# sensor_interface_1_1_0.net
KiCad netlist of a schematic drawn in EAGLE
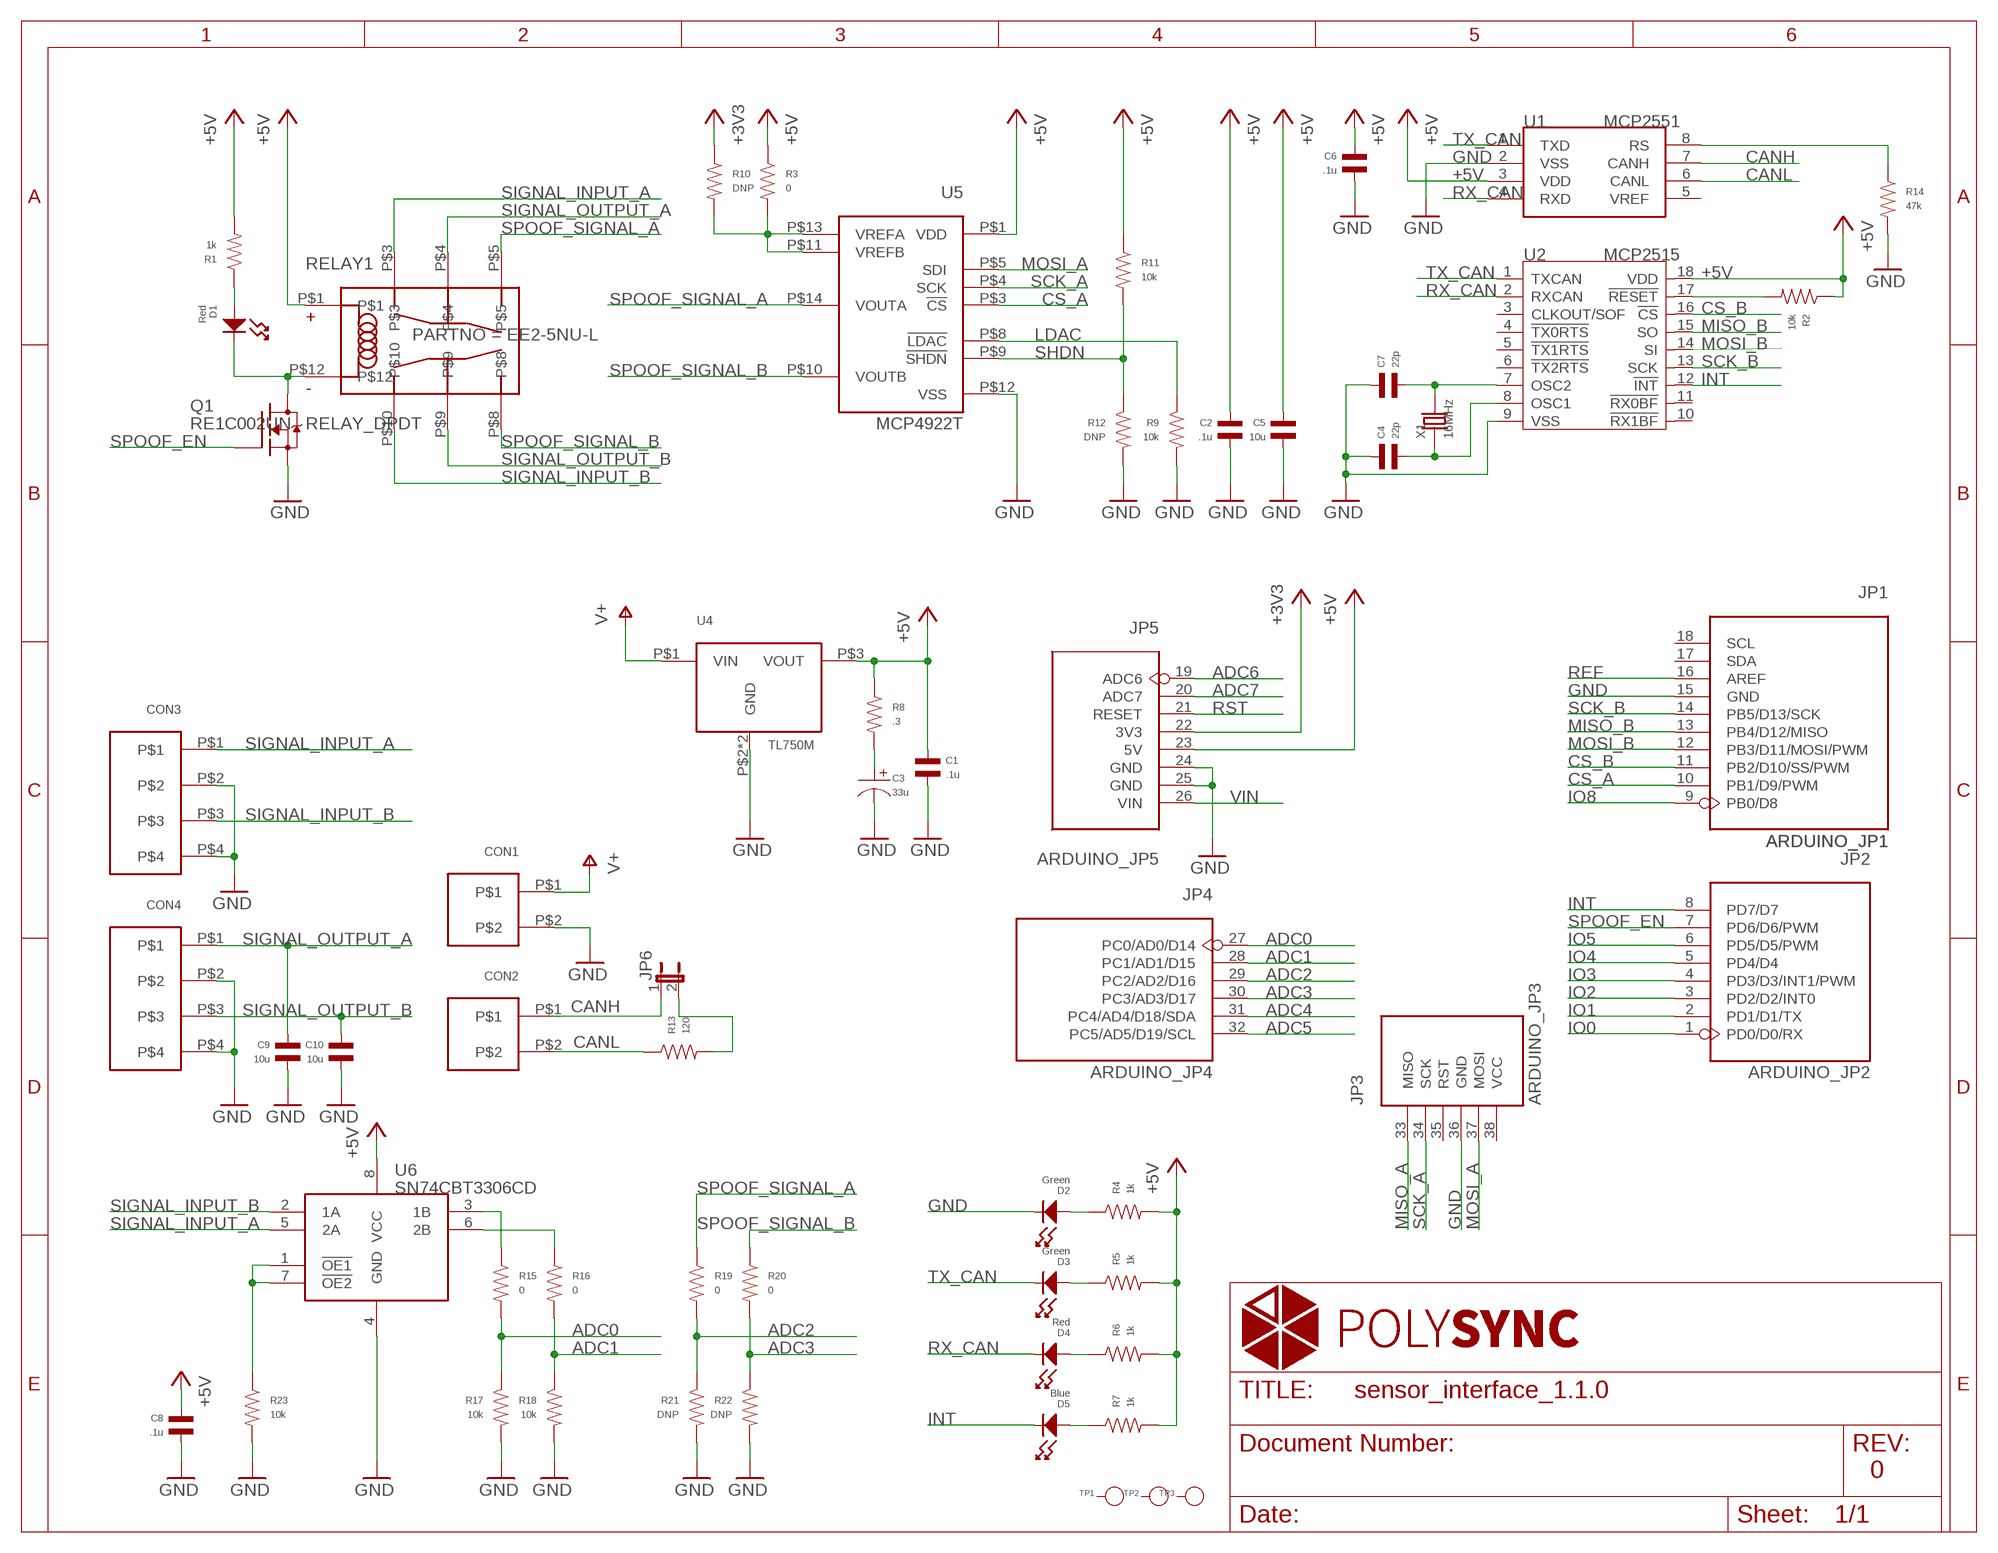
[diagram p0: schematic, sheet 1]

(export (version "E")
  (design (tool "Eeschema 10.0.6"))
  (components
    (comp (ref "C1")
      (value ".1u")
      (footprint "eagle-import:C0402")
      (libsource (lib "eagle-import") (part "CAPACITOR_NP_0402"))
    )
    (comp (ref "C2")
      (value ".1u")
      (footprint "eagle-import:C0402")
      (libsource (lib "eagle-import") (part "CAPACITOR_NP_0402"))
    )
    (comp (ref "C3")
      (value "33u")
      (footprint "eagle-import:CP1206")
      (libsource (lib "eagle-import") (part "CAPACITOR_P"))
    )
    (comp (ref "C4")
      (value "22p")
      (footprint "eagle-import:C0402")
      (libsource (lib "eagle-import") (part "CAPACITOR_NP_0402"))
    )
    (comp (ref "C5")
      (value "10u")
      (footprint "eagle-import:C0805")
      (libsource (lib "eagle-import") (part "CAPACITOR_NP_0805"))
    )
    (comp (ref "C6")
      (value ".1u")
      (footprint "eagle-import:C0402")
      (libsource (lib "eagle-import") (part "CAPACITOR_NP_0402"))
    )
    (comp (ref "C7")
      (value "22p")
      (footprint "eagle-import:C0402")
      (libsource (lib "eagle-import") (part "CAPACITOR_NP_0402"))
    )
    (comp (ref "C8")
      (value ".1u")
      (footprint "eagle-import:C0402")
      (libsource (lib "eagle-import") (part "CAPACITOR_NP_0402"))
    )
    (comp (ref "C9")
      (value "10u")
      (footprint "eagle-import:C0805")
      (libsource (lib "eagle-import") (part "CAPACITOR_NP_0805"))
    )
    (comp (ref "C10")
      (value "10u")
      (footprint "eagle-import:C0805")
      (libsource (lib "eagle-import") (part "CAPACITOR_NP_0805"))
    )
    (comp (ref "CON1")
      (value "CON23.5MM")
      (footprint "eagle-import:PHOENIX_2_45")
      (libsource (lib "eagle-import") (part "CON23.5MM"))
    )
    (comp (ref "CON2")
      (value "CON23.5MM")
      (footprint "eagle-import:PHOENIX_2_45")
      (libsource (lib "eagle-import") (part "CON23.5MM"))
    )
    (comp (ref "CON3")
      (value "CON4")
      (footprint "eagle-import:PHOENIX_4_45")
      (libsource (lib "eagle-import") (part "CON4"))
    )
    (comp (ref "CON4")
      (value "CON4")
      (footprint "eagle-import:PHOENIX_4_45")
      (libsource (lib "eagle-import") (part "CON4"))
    )
    (comp (ref "D1")
      (value "Red")
      (footprint "eagle-import:LED0603")
      (fields (field (name "HOUSEPART") "NO"))
      (libsource (lib "eagle-import") (part "LED_SINGLE-0603"))
    )
    (comp (ref "D2")
      (value "Green")
      (footprint "eagle-import:LED0603")
      (fields (field (name "HOUSEPART") "NO"))
      (libsource (lib "eagle-import") (part "LED_SINGLE-0603"))
    )
    (comp (ref "D3")
      (value "Green")
      (footprint "eagle-import:LED0603")
      (fields (field (name "HOUSEPART") "NO"))
      (libsource (lib "eagle-import") (part "LED_SINGLE-0603"))
    )
    (comp (ref "D4")
      (value "Red")
      (footprint "eagle-import:LED0603")
      (fields (field (name "HOUSEPART") "NO"))
      (libsource (lib "eagle-import") (part "LED_SINGLE-0603"))
    )
    (comp (ref "D5")
      (value "Blue")
      (footprint "eagle-import:LED0603")
      (fields (field (name "HOUSEPART") "NO"))
      (libsource (lib "eagle-import") (part "LED_SINGLE-0603"))
    )
    (comp (ref "JP1")
      (value "ARDUINO_JP1")
      (footprint "eagle-import:ARDUINO_JP1")
      (libsource (lib "eagle-import") (part "ARDUINO_JP1"))
    )
    (comp (ref "JP2")
      (value "ARDUINO_JP2")
      (footprint "eagle-import:ARDUINO_JP2")
      (libsource (lib "eagle-import") (part "ARDUINO_JP2"))
    )
    (comp (ref "JP3")
      (value "ARDUINO_JP3")
      (footprint "eagle-import:ARDUINO_JP3")
      (libsource (lib "eagle-import") (part "ARDUINO_JP3"))
    )
    (comp (ref "JP4")
      (value "ARDUINO_JP4")
      (footprint "eagle-import:ARDUINO_JP4")
      (libsource (lib "eagle-import") (part "ARDUINO_JP4"))
    )
    (comp (ref "JP5")
      (value "ARDUINO_JP5")
      (footprint "eagle-import:ARDUINO_JP5")
      (libsource (lib "eagle-import") (part "ARDUINO_JP5"))
    )
    (comp (ref "JP6")
      (value "JP1E")
      (footprint "eagle-import:JP1")
      (libsource (lib "eagle-import") (part "JP1E"))
    )
    (comp (ref "Q1")
      (value "RE1C002UN")
      (footprint "eagle-import:EMT3F")
      (libsource (lib "eagle-import") (part "RE1C002UN"))
    )
    (comp (ref "R1")
      (value "1k")
      (footprint "eagle-import:R0402")
      (libsource (lib "eagle-import") (part "RESISTOR_0402"))
    )
    (comp (ref "R2")
      (value "10k")
      (footprint "eagle-import:R0402")
      (libsource (lib "eagle-import") (part "RESISTOR_0402"))
    )
    (comp (ref "R3")
      (value "0")
      (footprint "eagle-import:R0402")
      (libsource (lib "eagle-import") (part "RESISTOR_0402"))
    )
    (comp (ref "R4")
      (value "1k")
      (footprint "eagle-import:R0402")
      (libsource (lib "eagle-import") (part "RESISTOR_0402"))
    )
    (comp (ref "R5")
      (value "1k")
      (footprint "eagle-import:R0402")
      (libsource (lib "eagle-import") (part "RESISTOR_0402"))
    )
    (comp (ref "R6")
      (value "1k")
      (footprint "eagle-import:R0402")
      (libsource (lib "eagle-import") (part "RESISTOR_0402"))
    )
    (comp (ref "R7")
      (value "1k")
      (footprint "eagle-import:R0402")
      (libsource (lib "eagle-import") (part "RESISTOR_0402"))
    )
    (comp (ref "R8")
      (value ".3")
      (footprint "eagle-import:R0402")
      (libsource (lib "eagle-import") (part "RESISTOR_0402"))
    )
    (comp (ref "R9")
      (value "10k")
      (footprint "eagle-import:R0402")
      (libsource (lib "eagle-import") (part "RESISTOR_0402"))
    )
    (comp (ref "R10")
      (value "DNP")
      (footprint "eagle-import:R0402")
      (libsource (lib "eagle-import") (part "RESISTOR_0402"))
    )
    (comp (ref "R11")
      (value "10k")
      (footprint "eagle-import:R0402")
      (libsource (lib "eagle-import") (part "RESISTOR_0402"))
    )
    (comp (ref "R12")
      (value "DNP")
      (footprint "eagle-import:R0402")
      (libsource (lib "eagle-import") (part "RESISTOR_0402"))
    )
    (comp (ref "R13")
      (value "120")
      (footprint "eagle-import:R0402")
      (libsource (lib "eagle-import") (part "RESISTOR_0402"))
    )
    (comp (ref "R14")
      (value "47k")
      (footprint "eagle-import:R0402")
      (libsource (lib "eagle-import") (part "RESISTOR_0402"))
    )
    (comp (ref "R15")
      (value "0")
      (footprint "eagle-import:R0402")
      (libsource (lib "eagle-import") (part "RESISTOR_0402"))
    )
    (comp (ref "R16")
      (value "0")
      (footprint "eagle-import:R0402")
      (libsource (lib "eagle-import") (part "RESISTOR_0402"))
    )
    (comp (ref "R17")
      (value "10k")
      (footprint "eagle-import:R0402")
      (libsource (lib "eagle-import") (part "RESISTOR_0402"))
    )
    (comp (ref "R18")
      (value "10k")
      (footprint "eagle-import:R0402")
      (libsource (lib "eagle-import") (part "RESISTOR_0402"))
    )
    (comp (ref "R19")
      (value "0")
      (footprint "eagle-import:R0402")
      (libsource (lib "eagle-import") (part "RESISTOR_0402"))
    )
    (comp (ref "R20")
      (value "0")
      (footprint "eagle-import:R0402")
      (libsource (lib "eagle-import") (part "RESISTOR_0402"))
    )
    (comp (ref "R21")
      (value "DNP")
      (footprint "eagle-import:R0402")
      (libsource (lib "eagle-import") (part "RESISTOR_0402"))
    )
    (comp (ref "R22")
      (value "DNP")
      (footprint "eagle-import:R0402")
      (libsource (lib "eagle-import") (part "RESISTOR_0402"))
    )
    (comp (ref "R23")
      (value "10k")
      (footprint "eagle-import:R0402")
      (libsource (lib "eagle-import") (part "RESISTOR_0402"))
    )
    (comp (ref "RELAY1")
      (value "RELAY_DPDT")
      (footprint "eagle-import:KEMET_EE2")
      (fields (field (name "PARTNO") "EE2-5NU-L"))
      (libsource (lib "eagle-import") (part "RELAY_DPDT"))
    )
    (comp (ref "TP1")
      (value "PAD-TEST-POINT'4545'")
      (footprint "eagle-import:TP_4545")
      (fields (field (name "PARTNO") "DNP"))
      (libsource (lib "eagle-import") (part "PAD-TEST-POINT'4545'"))
    )
    (comp (ref "TP2")
      (value "PAD-TEST-POINT'4545'")
      (footprint "eagle-import:TP_4545")
      (fields (field (name "PARTNO") "DNP"))
      (libsource (lib "eagle-import") (part "PAD-TEST-POINT'4545'"))
    )
    (comp (ref "TP3")
      (value "PAD-TEST-POINT'4545'")
      (footprint "eagle-import:TP_4545")
      (fields (field (name "PARTNO") "DNP"))
      (libsource (lib "eagle-import") (part "PAD-TEST-POINT'4545'"))
    )
    (comp (ref "U1")
      (value "MCP2551")
      (footprint "eagle-import:SOIC8-6.0")
      (libsource (lib "eagle-import") (part "MCP2551-SOIC8"))
    )
    (comp (ref "U2")
      (value "MCP2515")
      (footprint "eagle-import:SOIC18")
      (libsource (lib "eagle-import") (part "MCP2515-SOIC18"))
    )
    (comp (ref "U4")
      (value "TL750M")
      (footprint "eagle-import:TO-263")
      (libsource (lib "eagle-import") (part "TL750M"))
    )
    (comp (ref "U5")
      (value "MCP4922T")
      (footprint "eagle-import:TSSOP-14")
      (libsource (lib "eagle-import") (part "MCP4922T"))
    )
    (comp (ref "U6")
      (value "SN74CBT3306CD")
      (footprint "eagle-import:SOIC-8")
      (libsource (lib "eagle-import") (part "SN74CBT3306CD"))
    )
    (comp (ref "X1")
      (value "16MHz")
      (footprint "eagle-import:HC49UP")
      (libsource (lib "eagle-import") (part "CRYSTAL-HC49UP"))
    )
  )
  (nets
    (net (code "1") (name "+3V3") (class "Default")
      (node (ref "JP5") (pin "22") (pinfunction "3V3_22") (pintype "bidirectional"))
      (node (ref "R10") (pin "P$1") (pinfunction "P$1_P$1") (pintype "passive"))
    )
    (net (code "2") (name "+5V") (class "Default")
      (node (ref "C1") (pin "P$1") (pinfunction "P$1_P$1") (pintype "passive"))
      (node (ref "C2") (pin "P$1") (pinfunction "P$1_P$1") (pintype "passive"))
      (node (ref "C5") (pin "P$1") (pinfunction "P$1_P$1") (pintype "passive"))
      (node (ref "C6") (pin "P$1") (pinfunction "P$1_P$1") (pintype "passive"))
      (node (ref "C8") (pin "P$1") (pinfunction "P$1_P$1") (pintype "passive"))
      (node (ref "JP5") (pin "23") (pinfunction "5V_23") (pintype "bidirectional"))
      (node (ref "R1") (pin "P$2") (pinfunction "P$2_P$2") (pintype "passive"))
      (node (ref "R11") (pin "P$1") (pinfunction "P$1_P$1") (pintype "passive"))
      (node (ref "R2") (pin "P$1") (pinfunction "P$1_P$1") (pintype "passive"))
      (node (ref "R3") (pin "P$1") (pinfunction "P$1_P$1") (pintype "passive"))
      (node (ref "R4") (pin "P$2") (pinfunction "P$2_P$2") (pintype "passive"))
      (node (ref "R5") (pin "P$2") (pinfunction "P$2_P$2") (pintype "passive"))
      (node (ref "R6") (pin "P$2") (pinfunction "P$2_P$2") (pintype "passive"))
      (node (ref "R7") (pin "P$2") (pinfunction "P$2_P$2") (pintype "passive"))
      (node (ref "R8") (pin "P$1") (pinfunction "P$1_P$1") (pintype "passive"))
      (node (ref "RELAY1") (pin "P$1") (pinfunction "P$1_P$1") (pintype "bidirectional"))
      (node (ref "U1") (pin "3") (pinfunction "VDD_3") (pintype "bidirectional"))
      (node (ref "U2") (pin "18") (pinfunction "VDD_18") (pintype "power_in"))
      (node (ref "U4") (pin "P$3") (pinfunction "VOUT_P$3") (pintype "bidirectional"))
      (node (ref "U5") (pin "P$1") (pinfunction "VDD_P$1") (pintype "bidirectional"))
      (node (ref "U6") (pin "8") (pinfunction "VCC_8") (pintype "bidirectional"))
    )
    (net (code "3") (name "/ADC0") (class "Default")
      (node (ref "JP4") (pin "27") (pinfunction "PC0/AD0/D14_27") (pintype "bidirectional"))
      (node (ref "R15") (pin "P$2") (pinfunction "P$2_P$2") (pintype "passive"))
      (node (ref "R17") (pin "P$1") (pinfunction "P$1_P$1") (pintype "passive"))
    )
    (net (code "4") (name "/ADC1") (class "Default")
      (node (ref "JP4") (pin "28") (pinfunction "PC1/AD1/D15_28") (pintype "bidirectional"))
      (node (ref "R16") (pin "P$2") (pinfunction "P$2_P$2") (pintype "passive"))
      (node (ref "R18") (pin "P$1") (pinfunction "P$1_P$1") (pintype "passive"))
    )
    (net (code "5") (name "/ADC2") (class "Default")
      (node (ref "JP4") (pin "29") (pinfunction "PC2/AD2/D16_29") (pintype "bidirectional"))
      (node (ref "R19") (pin "P$2") (pinfunction "P$2_P$2") (pintype "passive"))
      (node (ref "R21") (pin "P$1") (pinfunction "P$1_P$1") (pintype "passive"))
    )
    (net (code "6") (name "/ADC3") (class "Default")
      (node (ref "JP4") (pin "30") (pinfunction "PC3/AD3/D17_30") (pintype "bidirectional"))
      (node (ref "R20") (pin "P$2") (pinfunction "P$2_P$2") (pintype "passive"))
      (node (ref "R22") (pin "P$1") (pinfunction "P$1_P$1") (pintype "passive"))
    )
    (net (code "7") (name "/ADC4") (class "Default")
      (node (ref "JP4") (pin "31") (pinfunction "PC4/AD4/D18/SDA_31") (pintype "bidirectional"))
    )
    (net (code "8") (name "/ADC5") (class "Default")
      (node (ref "JP4") (pin "32") (pinfunction "PC5/AD5/D19/SCL_32") (pintype "bidirectional"))
    )
    (net (code "9") (name "/ADC6") (class "Default")
      (node (ref "JP5") (pin "19") (pinfunction "ADC6_19") (pintype "bidirectional"))
    )
    (net (code "10") (name "/ADC7") (class "Default")
      (node (ref "JP5") (pin "20") (pinfunction "ADC7_20") (pintype "bidirectional"))
    )
    (net (code "11") (name "/CANH") (class "Default")
      (node (ref "CON2") (pin "P$1") (pinfunction "P$1_P$1") (pintype "bidirectional"))
      (node (ref "JP6") (pin "1") (pinfunction "1_1") (pintype "passive"))
      (node (ref "U1") (pin "7") (pinfunction "CANH_7") (pintype "bidirectional"))
    )
    (net (code "12") (name "/CANL") (class "Default")
      (node (ref "CON2") (pin "P$2") (pinfunction "P$2_P$2") (pintype "bidirectional"))
      (node (ref "R13") (pin "P$1") (pinfunction "P$1_P$1") (pintype "passive"))
      (node (ref "U1") (pin "6") (pinfunction "CANL_6") (pintype "bidirectional"))
    )
    (net (code "13") (name "/CS_A") (class "Default")
      (node (ref "JP1") (pin "10") (pinfunction "PB1/D9/PWM_10") (pintype "bidirectional"))
      (node (ref "U5") (pin "P$3") (pinfunction "~{CS}_P$3") (pintype "bidirectional"))
    )
    (net (code "14") (name "/CS_B") (class "Default")
      (node (ref "JP1") (pin "11") (pinfunction "PB2/D10/SS/PWM_11") (pintype "bidirectional"))
      (node (ref "U2") (pin "16") (pinfunction "~{CS}_16") (pintype "input"))
    )
    (net (code "15") (name "/INT") (class "Default")
      (node (ref "D5") (pin "CATHODE") (pinfunction "CATHODE_CATHODE") (pintype "power_in"))
      (node (ref "JP2") (pin "8") (pinfunction "PD7/D7_8") (pintype "bidirectional"))
      (node (ref "U2") (pin "12") (pinfunction "~{INT}_12") (pintype "output"))
    )
    (net (code "16") (name "/IO0") (class "Default")
      (node (ref "JP2") (pin "1") (pinfunction "PD0/D0/RX_1") (pintype "bidirectional"))
    )
    (net (code "17") (name "/IO1") (class "Default")
      (node (ref "JP2") (pin "2") (pinfunction "PD1/D1/TX_2") (pintype "bidirectional"))
    )
    (net (code "18") (name "/IO2") (class "Default")
      (node (ref "JP2") (pin "3") (pinfunction "PD2/D2/INT0_3") (pintype "bidirectional"))
    )
    (net (code "19") (name "/IO3") (class "Default")
      (node (ref "JP2") (pin "4") (pinfunction "PD3/D3/INT1/PWM_4") (pintype "bidirectional"))
    )
    (net (code "20") (name "/IO4") (class "Default")
      (node (ref "JP2") (pin "5") (pinfunction "PD4/D4_5") (pintype "bidirectional"))
    )
    (net (code "21") (name "/IO5") (class "Default")
      (node (ref "JP2") (pin "6") (pinfunction "PD5/D5/PWM_6") (pintype "bidirectional"))
    )
    (net (code "22") (name "/IO8") (class "Default")
      (node (ref "JP1") (pin "9") (pinfunction "PB0/D8_9") (pintype "bidirectional"))
    )
    (net (code "23") (name "/LDAC") (class "Default")
      (node (ref "R9") (pin "P$1") (pinfunction "P$1_P$1") (pintype "passive"))
      (node (ref "U5") (pin "P$8") (pinfunction "~{LDAC}_P$8") (pintype "bidirectional"))
    )
    (net (code "24") (name "/MISO_A") (class "Default")
      (node (ref "JP3") (pin "33") (pinfunction "MISO_33") (pintype "bidirectional"))
    )
    (net (code "25") (name "/MISO_B") (class "Default")
      (node (ref "JP1") (pin "13") (pinfunction "PB4/D12/MISO_13") (pintype "bidirectional"))
      (node (ref "U2") (pin "15") (pinfunction "SO_15") (pintype "output"))
    )
    (net (code "26") (name "/MOSI_A") (class "Default")
      (node (ref "JP3") (pin "37") (pinfunction "MOSI_37") (pintype "bidirectional"))
      (node (ref "U5") (pin "P$5") (pinfunction "SDI_P$5") (pintype "bidirectional"))
    )
    (net (code "27") (name "/MOSI_B") (class "Default")
      (node (ref "JP1") (pin "12") (pinfunction "PB3/D11/MOSI/PWM_12") (pintype "bidirectional"))
      (node (ref "U2") (pin "14") (pinfunction "SI_14") (pintype "input"))
    )
    (net (code "28") (name "/REF") (class "Default")
      (node (ref "JP1") (pin "16") (pinfunction "AREF_16") (pintype "bidirectional"))
    )
    (net (code "29") (name "/RST") (class "Default")
      (node (ref "JP5") (pin "21") (pinfunction "RESET_21") (pintype "bidirectional"))
    )
    (net (code "30") (name "/RX_CAN") (class "Default")
      (node (ref "D4") (pin "CATHODE") (pinfunction "CATHODE_CATHODE") (pintype "power_in"))
      (node (ref "U1") (pin "4") (pinfunction "RXD_4") (pintype "bidirectional"))
      (node (ref "U2") (pin "2") (pinfunction "RXCAN_2") (pintype "input"))
    )
    (net (code "31") (name "/SCK_A") (class "Default")
      (node (ref "JP3") (pin "34") (pinfunction "SCK_34") (pintype "bidirectional"))
      (node (ref "U5") (pin "P$4") (pinfunction "SCK_P$4") (pintype "bidirectional"))
    )
    (net (code "32") (name "/SCK_B") (class "Default")
      (node (ref "JP1") (pin "14") (pinfunction "PB5/D13/SCK_14") (pintype "bidirectional"))
      (node (ref "U2") (pin "13") (pinfunction "SCK_13") (pintype "input"))
    )
    (net (code "33") (name "/SHDN") (class "Default")
      (node (ref "R11") (pin "P$2") (pinfunction "P$2_P$2") (pintype "passive"))
      (node (ref "R12") (pin "P$1") (pinfunction "P$1_P$1") (pintype "passive"))
      (node (ref "U5") (pin "P$9") (pinfunction "~{SHDN}_P$9") (pintype "bidirectional"))
    )
    (net (code "34") (name "/SIGNAL_INPUT_A") (class "Default")
      (node (ref "CON3") (pin "P$1") (pinfunction "P$1_P$1") (pintype "bidirectional"))
      (node (ref "RELAY1") (pin "P$3") (pinfunction "P$3_P$3") (pintype "bidirectional"))
      (node (ref "U6") (pin "5") (pinfunction "2A_5") (pintype "bidirectional"))
    )
    (net (code "35") (name "/SIGNAL_INPUT_B") (class "Default")
      (node (ref "CON3") (pin "P$3") (pinfunction "P$3_P$3") (pintype "bidirectional"))
      (node (ref "RELAY1") (pin "P$10") (pinfunction "P$10_P$10") (pintype "bidirectional"))
      (node (ref "U6") (pin "2") (pinfunction "1A_2") (pintype "bidirectional"))
    )
    (net (code "36") (name "/SIGNAL_OUTPUT_A") (class "Default")
      (node (ref "C9") (pin "P$1") (pinfunction "P$1_P$1") (pintype "passive"))
      (node (ref "CON4") (pin "P$1") (pinfunction "P$1_P$1") (pintype "bidirectional"))
      (node (ref "RELAY1") (pin "P$4") (pinfunction "P$4_P$4") (pintype "bidirectional"))
    )
    (net (code "37") (name "/SIGNAL_OUTPUT_B") (class "Default")
      (node (ref "C10") (pin "P$1") (pinfunction "P$1_P$1") (pintype "passive"))
      (node (ref "CON4") (pin "P$3") (pinfunction "P$3_P$3") (pintype "bidirectional"))
      (node (ref "RELAY1") (pin "P$9") (pinfunction "P$9_P$9") (pintype "bidirectional"))
    )
    (net (code "38") (name "/SPOOF_EN") (class "Default")
      (node (ref "JP2") (pin "7") (pinfunction "PD6/D6/PWM_7") (pintype "bidirectional"))
      (node (ref "Q1") (pin "P$1") (pinfunction "G_P$1") (pintype "passive"))
    )
    (net (code "39") (name "/SPOOF_SIGNAL_A") (class "Default")
      (node (ref "R19") (pin "P$1") (pinfunction "P$1_P$1") (pintype "passive"))
      (node (ref "RELAY1") (pin "P$5") (pinfunction "P$5_P$5") (pintype "bidirectional"))
      (node (ref "U5") (pin "P$14") (pinfunction "VOUTA_P$14") (pintype "bidirectional"))
    )
    (net (code "40") (name "/SPOOF_SIGNAL_B") (class "Default")
      (node (ref "R20") (pin "P$1") (pinfunction "P$1_P$1") (pintype "passive"))
      (node (ref "RELAY1") (pin "P$8") (pinfunction "P$8_P$8") (pintype "bidirectional"))
      (node (ref "U5") (pin "P$10") (pinfunction "VOUTB_P$10") (pintype "bidirectional"))
    )
    (net (code "41") (name "/TX_CAN") (class "Default")
      (node (ref "D3") (pin "CATHODE") (pinfunction "CATHODE_CATHODE") (pintype "power_in"))
      (node (ref "U1") (pin "1") (pinfunction "TXD_1") (pintype "bidirectional"))
      (node (ref "U2") (pin "1") (pinfunction "TXCAN_1") (pintype "output"))
    )
    (net (code "42") (name "/VIN") (class "Default")
      (node (ref "JP5") (pin "26") (pinfunction "VIN_26") (pintype "bidirectional"))
    )
    (net (code "43") (name "GND") (class "Default")
      (node (ref "C1") (pin "P$2") (pinfunction "P$2_P$2") (pintype "passive"))
      (node (ref "C10") (pin "P$2") (pinfunction "P$2_P$2") (pintype "passive"))
      (node (ref "C2") (pin "P$2") (pinfunction "P$2_P$2") (pintype "passive"))
      (node (ref "C3") (pin "P$2") (pinfunction "P$2_P$2") (pintype "passive"))
      (node (ref "C4") (pin "P$1") (pinfunction "P$1_P$1") (pintype "passive"))
      (node (ref "C5") (pin "P$2") (pinfunction "P$2_P$2") (pintype "passive"))
      (node (ref "C6") (pin "P$2") (pinfunction "P$2_P$2") (pintype "passive"))
      (node (ref "C7") (pin "P$1") (pinfunction "P$1_P$1") (pintype "passive"))
      (node (ref "C8") (pin "P$2") (pinfunction "P$2_P$2") (pintype "passive"))
      (node (ref "C9") (pin "P$2") (pinfunction "P$2_P$2") (pintype "passive"))
      (node (ref "CON1") (pin "P$2") (pinfunction "P$2_P$2") (pintype "bidirectional"))
      (node (ref "CON3") (pin "P$2") (pinfunction "P$2_P$2") (pintype "bidirectional"))
      (node (ref "CON3") (pin "P$4") (pinfunction "P$4_P$4") (pintype "bidirectional"))
      (node (ref "CON4") (pin "P$2") (pinfunction "P$2_P$2") (pintype "bidirectional"))
      (node (ref "CON4") (pin "P$4") (pinfunction "P$4_P$4") (pintype "bidirectional"))
      (node (ref "D2") (pin "CATHODE") (pinfunction "CATHODE_CATHODE") (pintype "power_in"))
      (node (ref "JP1") (pin "15") (pinfunction "GND_15") (pintype "bidirectional"))
      (node (ref "JP3") (pin "36") (pinfunction "GND_36") (pintype "bidirectional"))
      (node (ref "JP5") (pin "24") (pinfunction "GND_24") (pintype "bidirectional"))
      (node (ref "JP5") (pin "25") (pinfunction "GND_25") (pintype "bidirectional"))
      (node (ref "Q1") (pin "P$2") (pinfunction "S_P$2") (pintype "passive"))
      (node (ref "R12") (pin "P$2") (pinfunction "P$2_P$2") (pintype "passive"))
      (node (ref "R14") (pin "P$2") (pinfunction "P$2_P$2") (pintype "passive"))
      (node (ref "R17") (pin "P$2") (pinfunction "P$2_P$2") (pintype "passive"))
      (node (ref "R18") (pin "P$2") (pinfunction "P$2_P$2") (pintype "passive"))
      (node (ref "R21") (pin "P$2") (pinfunction "P$2_P$2") (pintype "passive"))
      (node (ref "R22") (pin "P$2") (pinfunction "P$2_P$2") (pintype "passive"))
      (node (ref "R23") (pin "P$2") (pinfunction "P$2_P$2") (pintype "passive"))
      (node (ref "R9") (pin "P$2") (pinfunction "P$2_P$2") (pintype "passive"))
      (node (ref "U1") (pin "2") (pinfunction "VSS_2") (pintype "bidirectional"))
      (node (ref "U2") (pin "9") (pinfunction "VSS_9") (pintype "power_in"))
      (node (ref "U4") (pin "P$2") (pinfunction "GND_P$2") (pintype "bidirectional"))
      (node (ref "U4") (pin "P$4") (pinfunction "GND_P$4") (pintype "bidirectional"))
      (node (ref "U5") (pin "P$12") (pinfunction "VSS_P$12") (pintype "bidirectional"))
      (node (ref "U6") (pin "4") (pinfunction "GND_4") (pintype "bidirectional"))
    )
    (net (code "44") (name "Net-(C3-PadP$1)") (class "Default")
      (node (ref "C3") (pin "P$1") (pinfunction "P$1_P$1") (pintype "passive"))
      (node (ref "R8") (pin "P$2") (pinfunction "P$2_P$2") (pintype "passive"))
    )
    (net (code "45") (name "Net-(D1-PadANODE)") (class "Default")
      (node (ref "D1") (pin "ANODE") (pinfunction "ANODE_ANODE") (pintype "power_in"))
      (node (ref "R1") (pin "P$1") (pinfunction "P$1_P$1") (pintype "passive"))
    )
    (net (code "46") (name "Net-(D2-PadANODE)") (class "Default")
      (node (ref "D2") (pin "ANODE") (pinfunction "ANODE_ANODE") (pintype "power_in"))
      (node (ref "R4") (pin "P$1") (pinfunction "P$1_P$1") (pintype "passive"))
    )
    (net (code "47") (name "Net-(D3-PadANODE)") (class "Default")
      (node (ref "D3") (pin "ANODE") (pinfunction "ANODE_ANODE") (pintype "power_in"))
      (node (ref "R5") (pin "P$1") (pinfunction "P$1_P$1") (pintype "passive"))
    )
    (net (code "48") (name "Net-(D4-PadANODE)") (class "Default")
      (node (ref "D4") (pin "ANODE") (pinfunction "ANODE_ANODE") (pintype "power_in"))
      (node (ref "R6") (pin "P$1") (pinfunction "P$1_P$1") (pintype "passive"))
    )
    (net (code "49") (name "Net-(D5-PadANODE)") (class "Default")
      (node (ref "D5") (pin "ANODE") (pinfunction "ANODE_ANODE") (pintype "power_in"))
      (node (ref "R7") (pin "P$1") (pinfunction "P$1_P$1") (pintype "passive"))
    )
    (net (code "50") (name "Net-(JP6-Pad2)") (class "Default")
      (node (ref "JP6") (pin "2") (pinfunction "2_2") (pintype "passive"))
      (node (ref "R13") (pin "P$2") (pinfunction "P$2_P$2") (pintype "passive"))
    )
    (net (code "51") (name "Net-(Q1-D)") (class "Default")
      (node (ref "D1") (pin "CATHODE") (pinfunction "CATHODE_CATHODE") (pintype "power_in"))
      (node (ref "Q1") (pin "P$3") (pinfunction "D_P$3") (pintype "passive"))
      (node (ref "RELAY1") (pin "P$12") (pinfunction "P$12_P$12") (pintype "bidirectional"))
    )
    (net (code "52") (name "Net-(U1-RS)") (class "Default")
      (node (ref "R14") (pin "P$1") (pinfunction "P$1_P$1") (pintype "passive"))
      (node (ref "U1") (pin "8") (pinfunction "RS_8") (pintype "bidirectional"))
    )
    (net (code "53") (name "Net-(U2-OSC1)") (class "Default")
      (node (ref "C4") (pin "P$2") (pinfunction "P$2_P$2") (pintype "passive"))
      (node (ref "U2") (pin "8") (pinfunction "OSC1_8") (pintype "input"))
      (node (ref "X1") (pin "1") (pinfunction "1_1") (pintype "passive"))
    )
    (net (code "54") (name "Net-(U2-OSC2)") (class "Default")
      (node (ref "C7") (pin "P$2") (pinfunction "P$2_P$2") (pintype "passive"))
      (node (ref "U2") (pin "7") (pinfunction "OSC2_7") (pintype "output"))
      (node (ref "X1") (pin "2") (pinfunction "2_2") (pintype "passive"))
    )
    (net (code "55") (name "Net-(U2-~{RESET})") (class "Default")
      (node (ref "R2") (pin "P$2") (pinfunction "P$2_P$2") (pintype "passive"))
      (node (ref "U2") (pin "17") (pinfunction "~{RESET}_17") (pintype "input"))
    )
    (net (code "56") (name "Net-(U5-VREFA)") (class "Default")
      (node (ref "R10") (pin "P$2") (pinfunction "P$2_P$2") (pintype "passive"))
      (node (ref "R3") (pin "P$2") (pinfunction "P$2_P$2") (pintype "passive"))
      (node (ref "U5") (pin "P$11") (pinfunction "VREFB_P$11") (pintype "bidirectional"))
      (node (ref "U5") (pin "P$13") (pinfunction "VREFA_P$13") (pintype "bidirectional"))
    )
    (net (code "57") (name "Net-(U6-1B)") (class "Default")
      (node (ref "R15") (pin "P$1") (pinfunction "P$1_P$1") (pintype "passive"))
      (node (ref "U6") (pin "3") (pinfunction "1B_3") (pintype "bidirectional"))
    )
    (net (code "58") (name "Net-(U6-2B)") (class "Default")
      (node (ref "R16") (pin "P$1") (pinfunction "P$1_P$1") (pintype "passive"))
      (node (ref "U6") (pin "6") (pinfunction "2B_6") (pintype "bidirectional"))
    )
    (net (code "59") (name "Net-(U6-~{OE1})") (class "Default")
      (node (ref "R23") (pin "P$1") (pinfunction "P$1_P$1") (pintype "passive"))
      (node (ref "U6") (pin "1") (pinfunction "~{OE1}_1") (pintype "bidirectional"))
      (node (ref "U6") (pin "7") (pinfunction "~{OE2}_7") (pintype "bidirectional"))
    )
    (net (code "60") (name "V+") (class "Default")
      (node (ref "CON1") (pin "P$1") (pinfunction "P$1_P$1") (pintype "bidirectional"))
      (node (ref "U4") (pin "P$1") (pinfunction "VIN_P$1") (pintype "bidirectional"))
    )
    (net (code "61") (name "unconnected-(JP1-SCL-Pad18)") (class "Default")
      (node (ref "JP1") (pin "18") (pinfunction "SCL_18") (pintype "bidirectional"))
    )
    (net (code "62") (name "unconnected-(JP1-SDA-Pad17)") (class "Default")
      (node (ref "JP1") (pin "17") (pinfunction "SDA_17") (pintype "bidirectional"))
    )
    (net (code "63") (name "unconnected-(JP3-RST-Pad35)") (class "Default")
      (node (ref "JP3") (pin "35") (pinfunction "RST_35") (pintype "bidirectional"))
    )
    (net (code "64") (name "unconnected-(JP3-VCC-Pad38)") (class "Default")
      (node (ref "JP3") (pin "38") (pinfunction "VCC_38") (pintype "bidirectional"))
    )
    (net (code "65") (name "unconnected-(TP1-PadT)") (class "Default")
      (node (ref "TP1") (pin "T") (pinfunction "T_T") (pintype "bidirectional"))
    )
    (net (code "66") (name "unconnected-(TP2-PadT)") (class "Default")
      (node (ref "TP2") (pin "T") (pinfunction "T_T") (pintype "bidirectional"))
    )
    (net (code "67") (name "unconnected-(TP3-PadT)") (class "Default")
      (node (ref "TP3") (pin "T") (pinfunction "T_T") (pintype "bidirectional"))
    )
    (net (code "68") (name "unconnected-(U1-VREF-Pad5)") (class "Default")
      (node (ref "U1") (pin "5") (pinfunction "VREF_5") (pintype "bidirectional"))
    )
    (net (code "69") (name "unconnected-(U2-CLKOUT{slash}SOF-Pad3)") (class "Default")
      (node (ref "U2") (pin "3") (pinfunction "CLKOUT/SOF_3") (pintype "output"))
    )
    (net (code "70") (name "unconnected-(U2-~{RX0BF}-Pad11)") (class "Default")
      (node (ref "U2") (pin "11") (pinfunction "~{RX0BF}_11") (pintype "output"))
    )
    (net (code "71") (name "unconnected-(U2-~{RX1BF}-Pad10)") (class "Default")
      (node (ref "U2") (pin "10") (pinfunction "~{RX1BF}_10") (pintype "output"))
    )
    (net (code "72") (name "unconnected-(U2-~{TX0RTS}-Pad4)") (class "Default")
      (node (ref "U2") (pin "4") (pinfunction "~{TX0RTS}_4") (pintype "input"))
    )
    (net (code "73") (name "unconnected-(U2-~{TX1RTS}-Pad5)") (class "Default")
      (node (ref "U2") (pin "5") (pinfunction "~{TX1RTS}_5") (pintype "input"))
    )
    (net (code "74") (name "unconnected-(U2-~{TX2RTS}-Pad6)") (class "Default")
      (node (ref "U2") (pin "6") (pinfunction "~{TX2RTS}_6") (pintype "input"))
    )
  )
)
